# C3D_ReMix_Expansion_-_RJ45_Hat.net
KiCad netlist of a schematic drawn in EAGLE
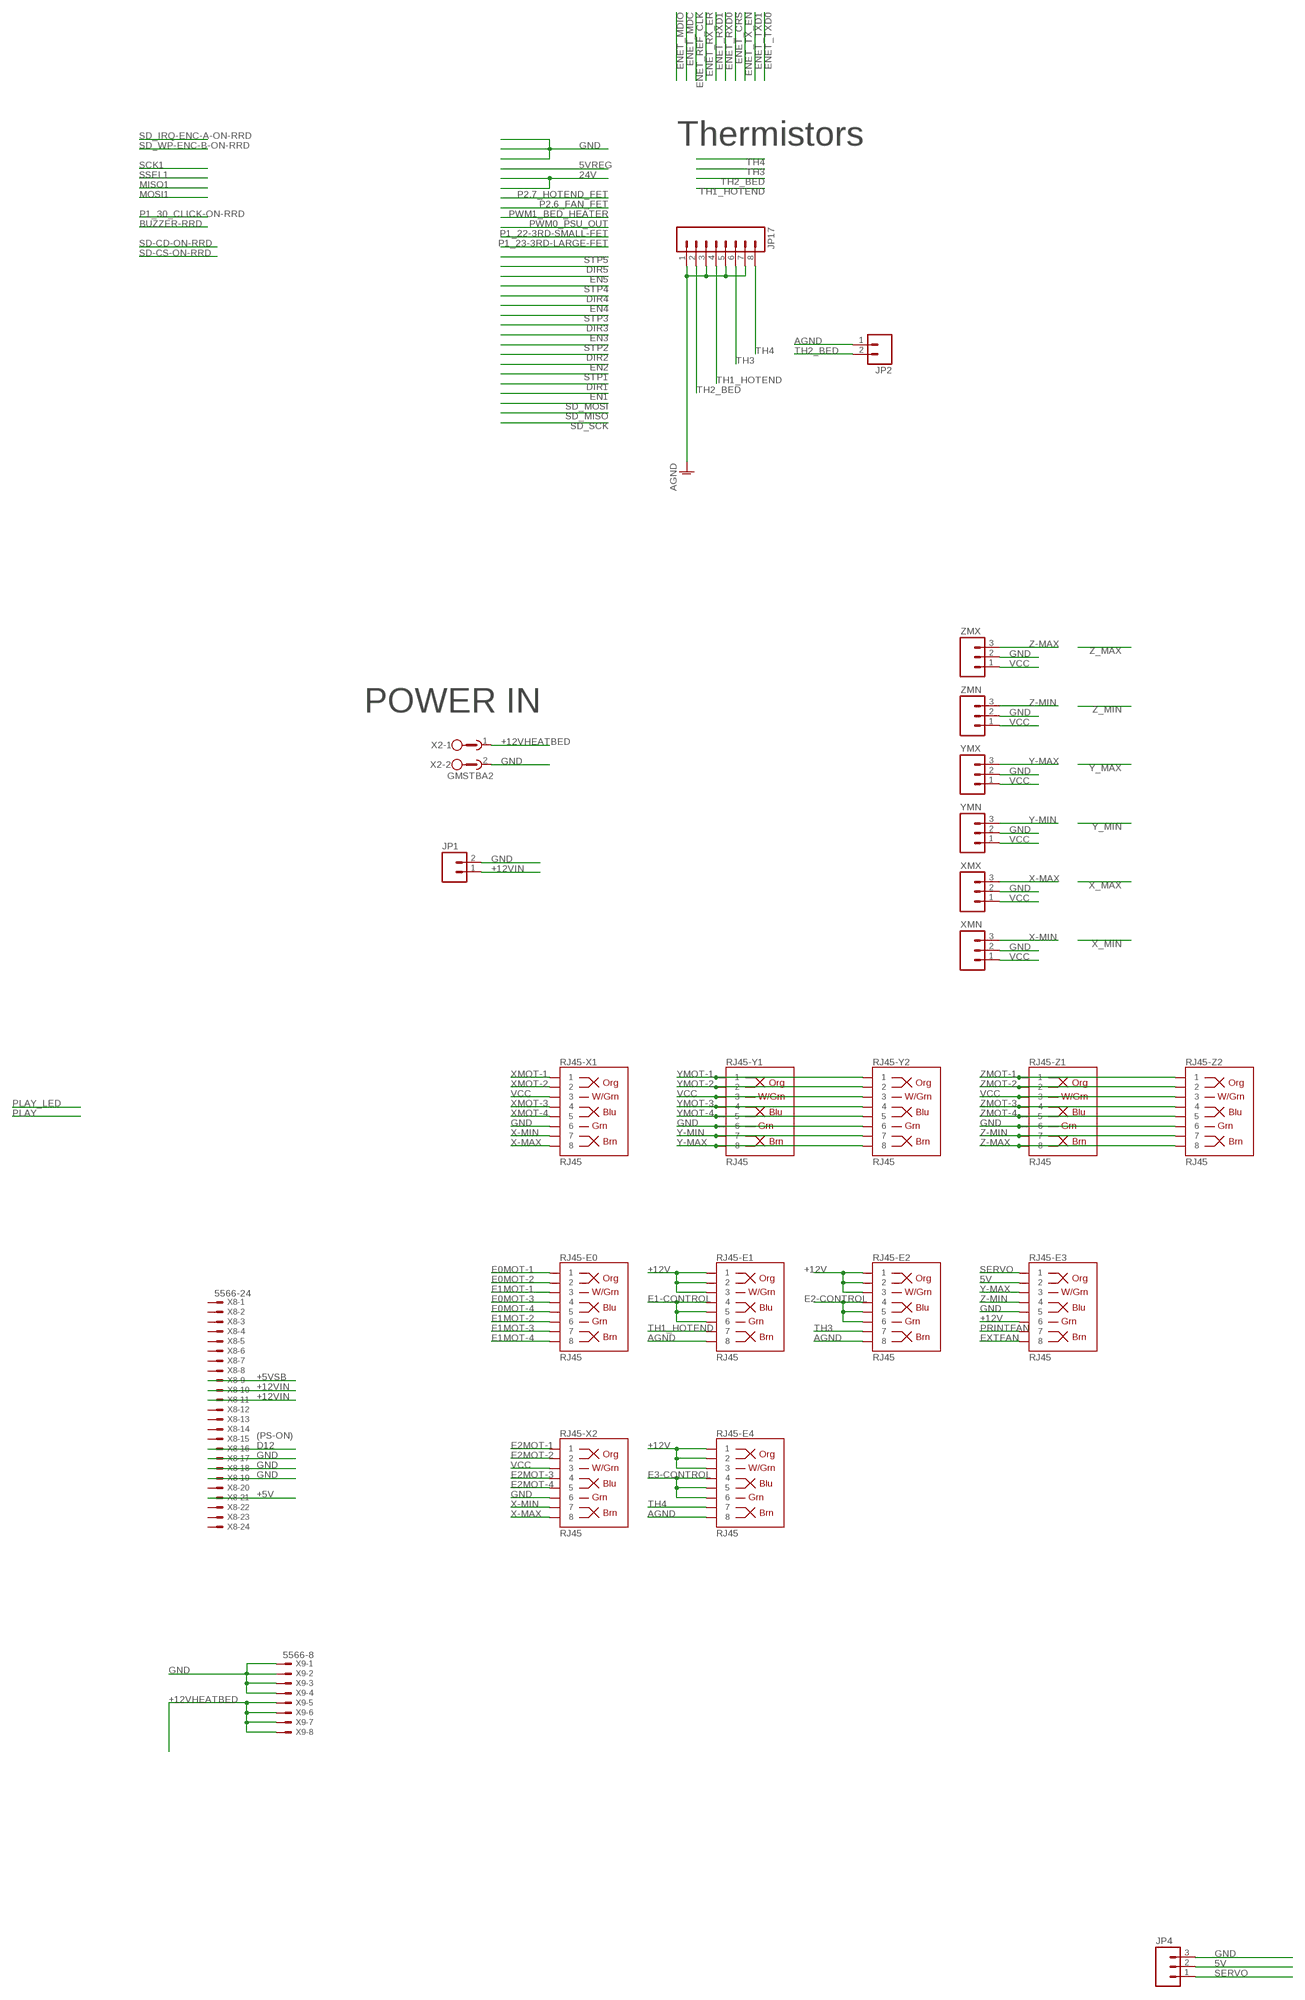
[diagram p0: schematic, sheet 1, part 1 of 2]
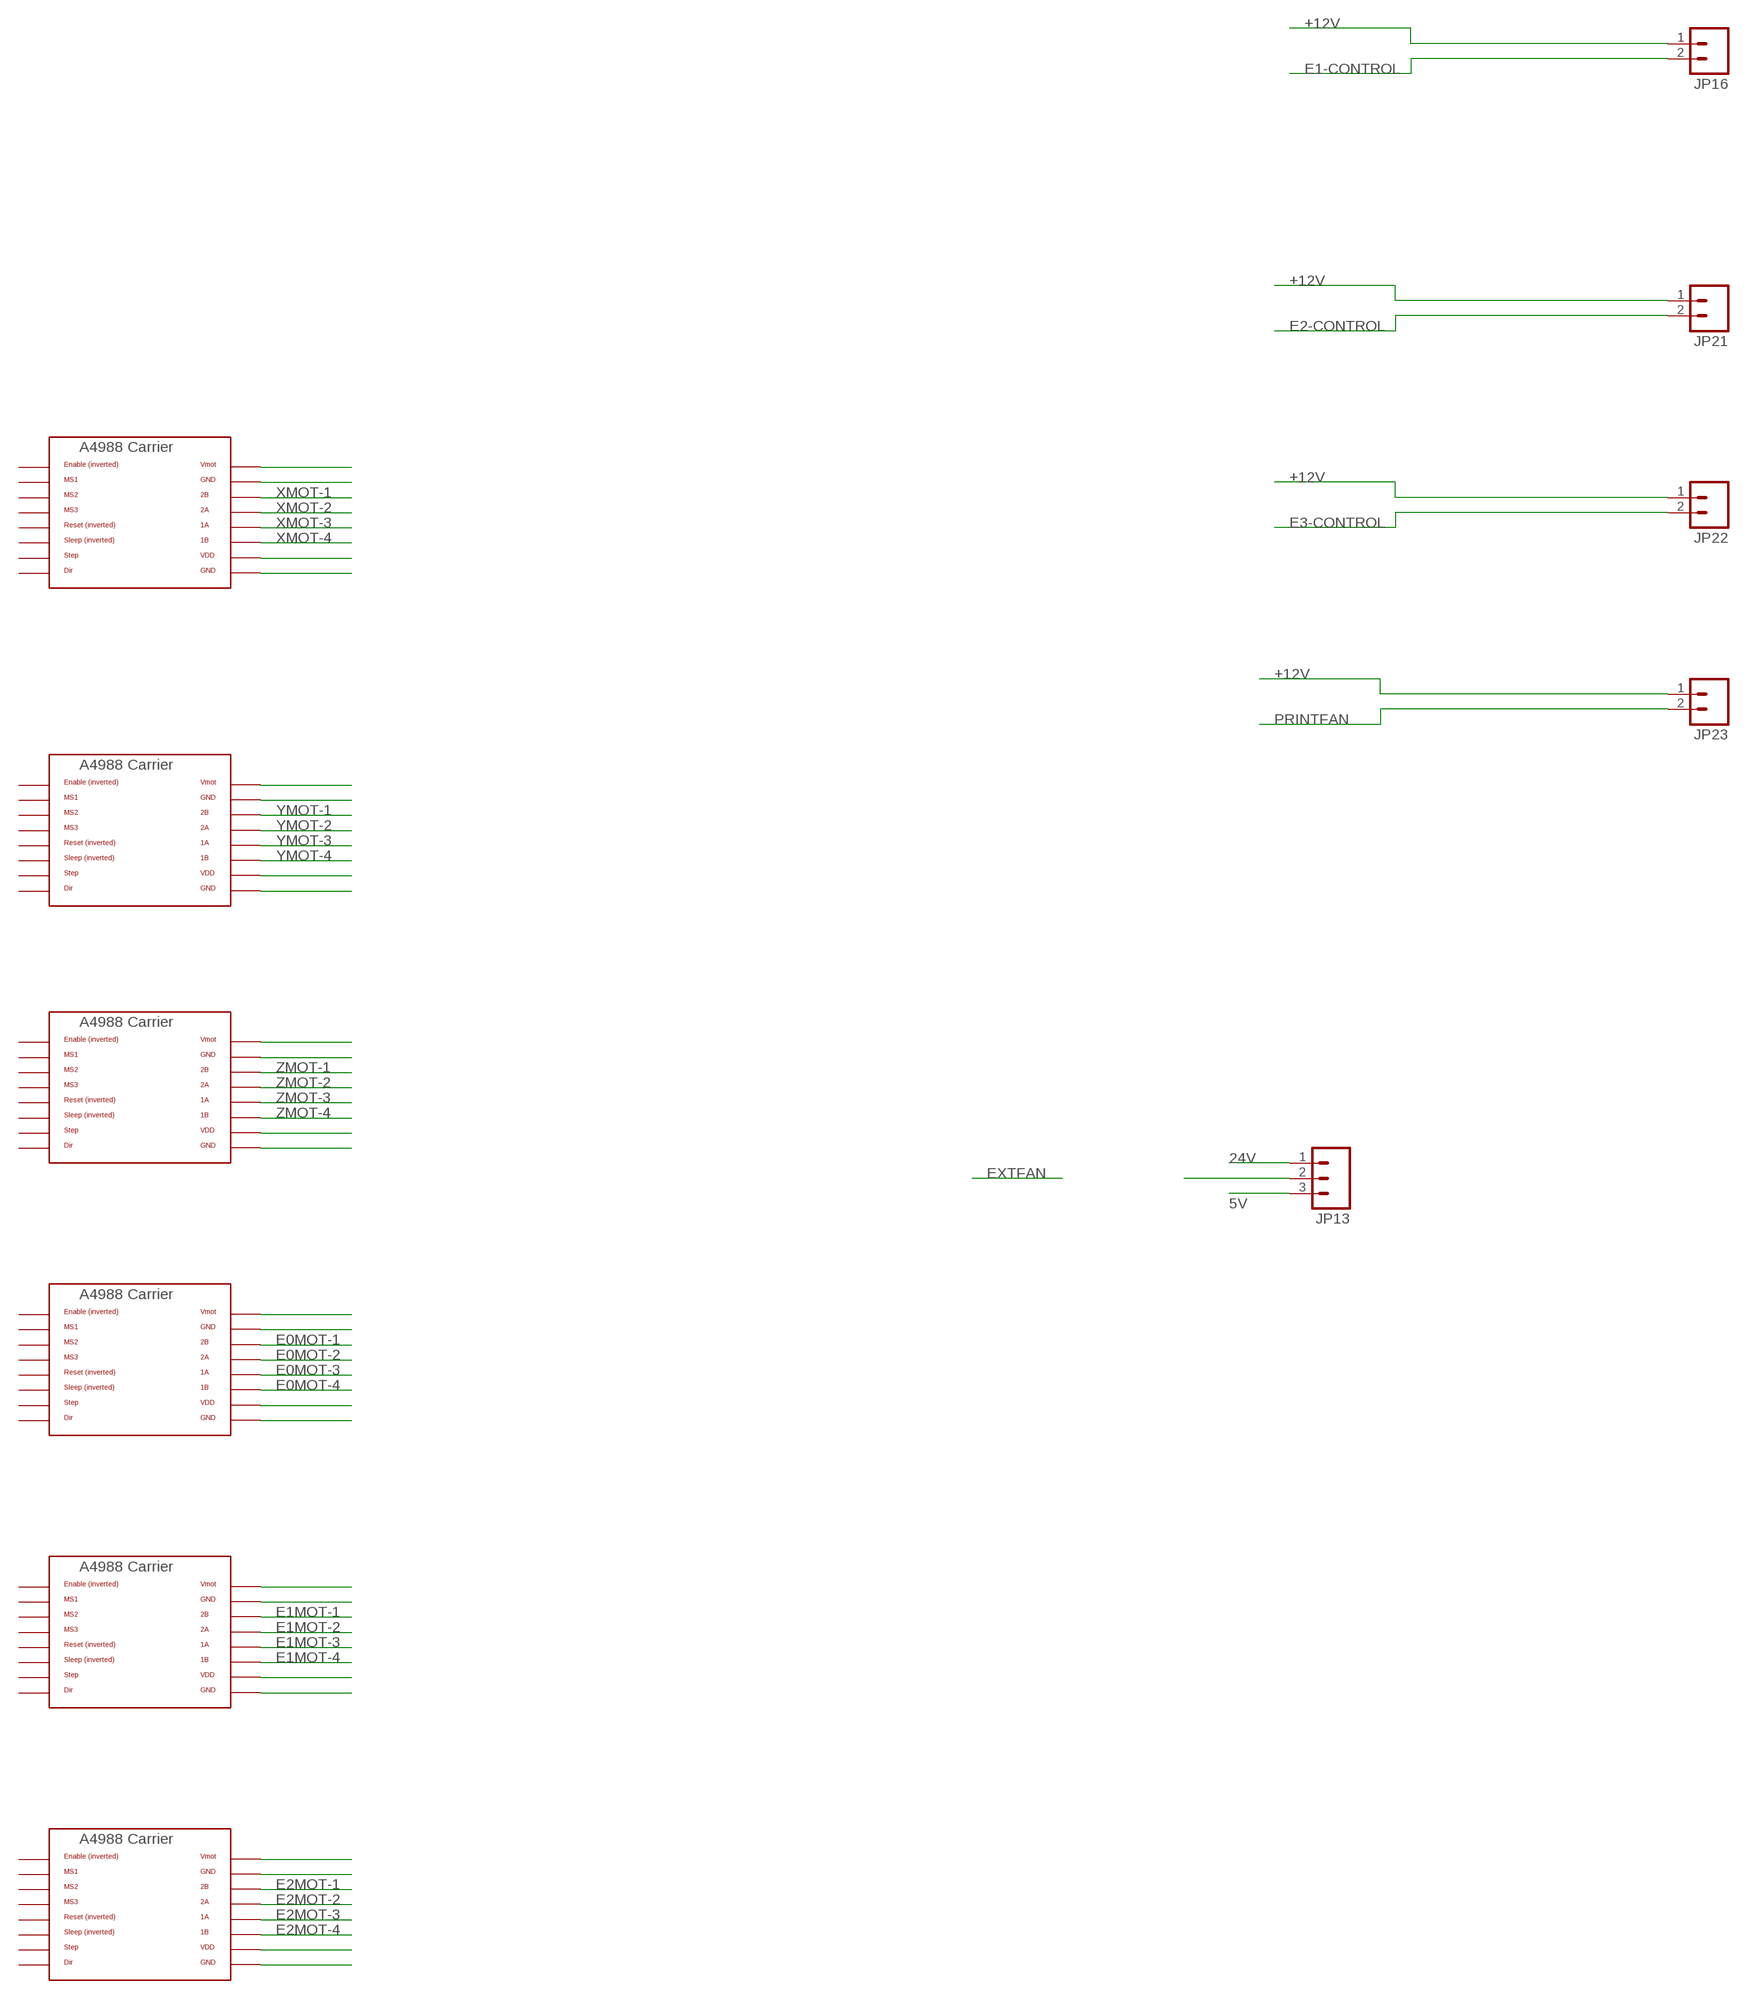
[diagram p1: schematic, sheet 1, part 2 of 2]

(export (version "E")
  (design (tool "Eeschema 10.0.6"))
  (components
    (comp (ref "JP1")
      (value "M025MM")
      (footprint "eagle-import:SCREWTERMINAL-5MM-2")
      (libsource (lib "eagle-import") (part "M025MM"))
    )
    (comp (ref "JP2")
      (value "M02LOCK")
      (footprint "eagle-import:1X02_LOCK")
      (libsource (lib "eagle-import") (part "M02LOCK"))
    )
    (comp (ref "JP4")
      (value "M03LOCK")
      (footprint "eagle-import:1X03_LOCK")
      (libsource (lib "eagle-import") (part "M03LOCK"))
    )
    (comp (ref "JP13")
      (value "M03LOCK_NO_SILK")
      (footprint "eagle-import:1X03_LOCK_NO_SILK")
      (libsource (lib "eagle-import") (part "M03LOCK_NO_SILK"))
    )
    (comp (ref "JP16")
      (value "M02LOCK")
      (footprint "eagle-import:1X02_LOCK")
      (libsource (lib "eagle-import") (part "M02LOCK"))
    )
    (comp (ref "JP17")
      (value "M08LOCK")
      (footprint "eagle-import:1X08_LOCK")
      (libsource (lib "eagle-import") (part "M08LOCK"))
    )
    (comp (ref "JP21")
      (value "M02LOCK")
      (footprint "eagle-import:1X02_LOCK")
      (libsource (lib "eagle-import") (part "M02LOCK"))
    )
    (comp (ref "JP22")
      (value "M02LOCK")
      (footprint "eagle-import:1X02_LOCK")
      (libsource (lib "eagle-import") (part "M02LOCK"))
    )
    (comp (ref "JP23")
      (value "M02LOCK")
      (footprint "eagle-import:1X02_LOCK")
      (libsource (lib "eagle-import") (part "M02LOCK"))
    )
    (comp (ref "RJ45-E0")
      (value "RJ45")
      (footprint "eagle-import:RJ45-8")
      (libsource (lib "eagle-import") (part "RJ45-8PTH"))
    )
    (comp (ref "RJ45-E1")
      (value "RJ45")
      (footprint "eagle-import:RJ45-8")
      (libsource (lib "eagle-import") (part "RJ45-8PTH"))
    )
    (comp (ref "RJ45-E2")
      (value "RJ45")
      (footprint "eagle-import:RJ45-8")
      (libsource (lib "eagle-import") (part "RJ45-8PTH"))
    )
    (comp (ref "RJ45-E3")
      (value "RJ45")
      (footprint "eagle-import:RJ45-8")
      (libsource (lib "eagle-import") (part "RJ45-8PTH"))
    )
    (comp (ref "RJ45-E4")
      (value "RJ45")
      (footprint "eagle-import:RJ45-8")
      (libsource (lib "eagle-import") (part "RJ45-8PTH"))
    )
    (comp (ref "RJ45-X1")
      (value "RJ45")
      (footprint "eagle-import:RJ45-8")
      (libsource (lib "eagle-import") (part "RJ45-8PTH"))
    )
    (comp (ref "RJ45-X2")
      (value "RJ45")
      (footprint "eagle-import:RJ45-8")
      (libsource (lib "eagle-import") (part "RJ45-8PTH"))
    )
    (comp (ref "RJ45-Y1")
      (value "RJ45")
      (footprint "eagle-import:RJ45-8")
      (libsource (lib "eagle-import") (part "RJ45-8PTH"))
    )
    (comp (ref "RJ45-Y2")
      (value "RJ45")
      (footprint "eagle-import:RJ45-8")
      (libsource (lib "eagle-import") (part "RJ45-8PTH"))
    )
    (comp (ref "RJ45-Z1")
      (value "RJ45")
      (footprint "eagle-import:RJ45-8")
      (libsource (lib "eagle-import") (part "RJ45-8PTH"))
    )
    (comp (ref "RJ45-Z2")
      (value "RJ45")
      (footprint "eagle-import:RJ45-8")
      (libsource (lib "eagle-import") (part "RJ45-8PTH"))
    )
    (comp (ref "U$1")
      (value "POLOLU_A4983CARRIER")
      (footprint "eagle-import:A4988BREAKOUT")
      (libsource (lib "eagle-import") (part "POLOLU_A4983CARRIER"))
    )
    (comp (ref "U$5")
      (value "POLOLU_A4983CARRIER")
      (footprint "eagle-import:A4988BREAKOUT")
      (libsource (lib "eagle-import") (part "POLOLU_A4983CARRIER"))
    )
    (comp (ref "U$6")
      (value "POLOLU_A4983CARRIER")
      (footprint "eagle-import:A4988BREAKOUT")
      (libsource (lib "eagle-import") (part "POLOLU_A4983CARRIER"))
    )
    (comp (ref "U$7")
      (value "POLOLU_A4983CARRIER")
      (footprint "eagle-import:A4988BREAKOUT")
      (libsource (lib "eagle-import") (part "POLOLU_A4983CARRIER"))
    )
    (comp (ref "U$8")
      (value "POLOLU_A4983CARRIER")
      (footprint "eagle-import:A4988BREAKOUT")
      (libsource (lib "eagle-import") (part "POLOLU_A4983CARRIER"))
    )
    (comp (ref "U$9")
      (value "POLOLU_A4983CARRIER")
      (footprint "eagle-import:A4988BREAKOUT")
      (libsource (lib "eagle-import") (part "POLOLU_A4983CARRIER"))
    )
    (comp (ref "X2")
      (value "GMSTBA2")
      (footprint "eagle-import:GMSTBA2")
      (fields (field (name "MF") "FARNELL") (field (name "MPN") "1757242"))
      (libsource (lib "eagle-import") (part "GMSTBA2"))
    )
    (comp (ref "X8")
      (value "5566-24")
      (footprint "eagle-import:5566-24")
      (libsource (lib "eagle-import") (part "5566-24"))
    )
    (comp (ref "X9")
      (value "5566-8")
      (footprint "eagle-import:5566-8")
      (libsource (lib "eagle-import") (part "5566-8"))
    )
    (comp (ref "XMN")
      (value "M03POLAR_LOCK")
      (footprint "eagle-import:MOLEX-1X3_LOCK")
      (libsource (lib "eagle-import") (part "M03POLAR_LOCK"))
    )
    (comp (ref "XMX")
      (value "M03POLAR_LOCK")
      (footprint "eagle-import:MOLEX-1X3_LOCK")
      (libsource (lib "eagle-import") (part "M03POLAR_LOCK"))
    )
    (comp (ref "YMN")
      (value "M03POLAR_LOCK")
      (footprint "eagle-import:MOLEX-1X3_LOCK")
      (libsource (lib "eagle-import") (part "M03POLAR_LOCK"))
    )
    (comp (ref "YMX")
      (value "M03POLAR_LOCK")
      (footprint "eagle-import:MOLEX-1X3_LOCK")
      (libsource (lib "eagle-import") (part "M03POLAR_LOCK"))
    )
    (comp (ref "ZMN")
      (value "M03POLAR_LOCK")
      (footprint "eagle-import:MOLEX-1X3_LOCK")
      (libsource (lib "eagle-import") (part "M03POLAR_LOCK"))
    )
    (comp (ref "ZMX")
      (value "M03POLAR_LOCK")
      (footprint "eagle-import:MOLEX-1X3_LOCK")
      (libsource (lib "eagle-import") (part "M03POLAR_LOCK"))
    )
  )
  (nets
    (net (code "1") (name "/+5V") (class "Default")
      (node (ref "X8") (pin "21") (pinfunction "S_21") (pintype "passive"))
    )
    (net (code "2") (name "/+5VSB") (class "Default")
      (node (ref "X8") (pin "9") (pinfunction "S_9") (pintype "passive"))
    )
    (net (code "3") (name "/+12V") (class "Default")
      (node (ref "JP16") (pin "1") (pinfunction "1_1") (pintype "passive"))
      (node (ref "JP21") (pin "1") (pinfunction "1_1") (pintype "passive"))
      (node (ref "JP22") (pin "1") (pinfunction "1_1") (pintype "passive"))
      (node (ref "JP23") (pin "1") (pinfunction "1_1") (pintype "passive"))
      (node (ref "RJ45-E1") (pin "1") (pinfunction "1_1") (pintype "bidirectional"))
      (node (ref "RJ45-E1") (pin "2") (pinfunction "2_2") (pintype "bidirectional"))
      (node (ref "RJ45-E1") (pin "3") (pinfunction "3_3") (pintype "bidirectional"))
      (node (ref "RJ45-E2") (pin "1") (pinfunction "1_1") (pintype "bidirectional"))
      (node (ref "RJ45-E2") (pin "2") (pinfunction "2_2") (pintype "bidirectional"))
      (node (ref "RJ45-E2") (pin "3") (pinfunction "3_3") (pintype "bidirectional"))
      (node (ref "RJ45-E3") (pin "6") (pinfunction "6_6") (pintype "bidirectional"))
      (node (ref "RJ45-E4") (pin "1") (pinfunction "1_1") (pintype "bidirectional"))
      (node (ref "RJ45-E4") (pin "2") (pinfunction "2_2") (pintype "bidirectional"))
      (node (ref "RJ45-E4") (pin "3") (pinfunction "3_3") (pintype "bidirectional"))
    )
    (net (code "4") (name "/+12VHEATBED") (class "Default")
      (node (ref "X2") (pin "1") (pinfunction "1_1") (pintype "passive"))
      (node (ref "X9") (pin "5") (pinfunction "S_5") (pintype "passive"))
      (node (ref "X9") (pin "6") (pinfunction "S_6") (pintype "passive"))
      (node (ref "X9") (pin "7") (pinfunction "S_7") (pintype "passive"))
      (node (ref "X9") (pin "8") (pinfunction "S_8") (pintype "passive"))
    )
    (net (code "5") (name "/+12VIN") (class "Default")
      (node (ref "JP1") (pin "1") (pinfunction "1_1") (pintype "passive"))
      (node (ref "X8") (pin "10") (pinfunction "S_10") (pintype "passive"))
      (node (ref "X8") (pin "11") (pinfunction "S_11") (pintype "passive"))
    )
    (net (code "6") (name "/5V") (class "Default")
      (node (ref "JP13") (pin "3") (pinfunction "3_3") (pintype "passive"))
      (node (ref "JP4") (pin "2") (pinfunction "2_2") (pintype "passive"))
      (node (ref "RJ45-E3") (pin "2") (pinfunction "2_2") (pintype "bidirectional"))
    )
    (net (code "8") (name "/24V") (class "Default")
      (node (ref "JP13") (pin "1") (pinfunction "1_1") (pintype "passive"))
    )
    (net (code "10") (name "/D12") (class "Default")
      (node (ref "X8") (pin "16") (pinfunction "S_16") (pintype "passive"))
    )
    (net (code "16") (name "/E0MOT-1") (class "Default")
      (node (ref "RJ45-E0") (pin "1") (pinfunction "1_1") (pintype "bidirectional"))
      (node (ref "U$7") (pin "2B") (pinfunction "2B_2B") (pintype "output"))
    )
    (net (code "17") (name "/E0MOT-2") (class "Default")
      (node (ref "RJ45-E0") (pin "2") (pinfunction "2_2") (pintype "bidirectional"))
      (node (ref "U$7") (pin "2A") (pinfunction "2A_2A") (pintype "output"))
    )
    (net (code "18") (name "/E0MOT-3") (class "Default")
      (node (ref "RJ45-E0") (pin "4") (pinfunction "4_4") (pintype "bidirectional"))
      (node (ref "U$7") (pin "1A") (pinfunction "1A_1A") (pintype "output"))
    )
    (net (code "19") (name "/E0MOT-4") (class "Default")
      (node (ref "RJ45-E0") (pin "5") (pinfunction "5_5") (pintype "bidirectional"))
      (node (ref "U$7") (pin "1B") (pinfunction "1B_1B") (pintype "output"))
    )
    (net (code "20") (name "/E1-CONTROL") (class "Default")
      (node (ref "JP16") (pin "2") (pinfunction "2_2") (pintype "passive"))
      (node (ref "RJ45-E1") (pin "4") (pinfunction "4_4") (pintype "bidirectional"))
      (node (ref "RJ45-E1") (pin "5") (pinfunction "5_5") (pintype "bidirectional"))
      (node (ref "RJ45-E1") (pin "6") (pinfunction "6_6") (pintype "bidirectional"))
    )
    (net (code "21") (name "/E1MOT-1") (class "Default")
      (node (ref "RJ45-E0") (pin "3") (pinfunction "3_3") (pintype "bidirectional"))
      (node (ref "U$8") (pin "2B") (pinfunction "2B_2B") (pintype "output"))
    )
    (net (code "22") (name "/E1MOT-2") (class "Default")
      (node (ref "RJ45-E0") (pin "6") (pinfunction "6_6") (pintype "bidirectional"))
      (node (ref "U$8") (pin "2A") (pinfunction "2A_2A") (pintype "output"))
    )
    (net (code "23") (name "/E1MOT-3") (class "Default")
      (node (ref "RJ45-E0") (pin "7") (pinfunction "7_7") (pintype "bidirectional"))
      (node (ref "U$8") (pin "1A") (pinfunction "1A_1A") (pintype "output"))
    )
    (net (code "24") (name "/E1MOT-4") (class "Default")
      (node (ref "RJ45-E0") (pin "8") (pinfunction "8_8") (pintype "bidirectional"))
      (node (ref "U$8") (pin "1B") (pinfunction "1B_1B") (pintype "output"))
    )
    (net (code "25") (name "/E2-CONTROL") (class "Default")
      (node (ref "JP21") (pin "2") (pinfunction "2_2") (pintype "passive"))
      (node (ref "RJ45-E2") (pin "4") (pinfunction "4_4") (pintype "bidirectional"))
      (node (ref "RJ45-E2") (pin "5") (pinfunction "5_5") (pintype "bidirectional"))
      (node (ref "RJ45-E2") (pin "6") (pinfunction "6_6") (pintype "bidirectional"))
    )
    (net (code "26") (name "/E2MOT-1") (class "Default")
      (node (ref "RJ45-X2") (pin "1") (pinfunction "1_1") (pintype "bidirectional"))
      (node (ref "U$9") (pin "2B") (pinfunction "2B_2B") (pintype "output"))
    )
    (net (code "27") (name "/E2MOT-2") (class "Default")
      (node (ref "RJ45-X2") (pin "2") (pinfunction "2_2") (pintype "bidirectional"))
      (node (ref "U$9") (pin "2A") (pinfunction "2A_2A") (pintype "output"))
    )
    (net (code "28") (name "/E2MOT-3") (class "Default")
      (node (ref "RJ45-X2") (pin "4") (pinfunction "4_4") (pintype "bidirectional"))
      (node (ref "U$9") (pin "1A") (pinfunction "1A_1A") (pintype "output"))
    )
    (net (code "29") (name "/E2MOT-4") (class "Default")
      (node (ref "RJ45-X2") (pin "5") (pinfunction "5_5") (pintype "bidirectional"))
      (node (ref "U$9") (pin "1B") (pinfunction "1B_1B") (pintype "output"))
    )
    (net (code "30") (name "/E3-CONTROL") (class "Default")
      (node (ref "JP22") (pin "2") (pinfunction "2_2") (pintype "passive"))
      (node (ref "RJ45-E4") (pin "4") (pinfunction "4_4") (pintype "bidirectional"))
      (node (ref "RJ45-E4") (pin "5") (pinfunction "5_5") (pintype "bidirectional"))
      (node (ref "RJ45-E4") (pin "6") (pinfunction "6_6") (pintype "bidirectional"))
    )
    (net (code "46") (name "/EXTFAN") (class "Default")
      (node (ref "RJ45-E3") (pin "8") (pinfunction "8_8") (pintype "bidirectional"))
    )
    (net (code "47") (name "/GND") (class "Default")
      (node (ref "JP1") (pin "2") (pinfunction "2_2") (pintype "passive"))
      (node (ref "JP4") (pin "3") (pinfunction "3_3") (pintype "passive"))
      (node (ref "RJ45-E3") (pin "5") (pinfunction "5_5") (pintype "bidirectional"))
      (node (ref "RJ45-X1") (pin "6") (pinfunction "6_6") (pintype "bidirectional"))
      (node (ref "RJ45-X2") (pin "6") (pinfunction "6_6") (pintype "bidirectional"))
      (node (ref "RJ45-Y1") (pin "6") (pinfunction "6_6") (pintype "bidirectional"))
      (node (ref "RJ45-Y2") (pin "6") (pinfunction "6_6") (pintype "bidirectional"))
      (node (ref "RJ45-Z1") (pin "6") (pinfunction "6_6") (pintype "bidirectional"))
      (node (ref "RJ45-Z2") (pin "6") (pinfunction "6_6") (pintype "bidirectional"))
      (node (ref "X2") (pin "2") (pinfunction "1_2") (pintype "passive"))
      (node (ref "X8") (pin "17") (pinfunction "S_17") (pintype "passive"))
      (node (ref "X8") (pin "18") (pinfunction "S_18") (pintype "passive"))
      (node (ref "X8") (pin "19") (pinfunction "S_19") (pintype "passive"))
      (node (ref "X9") (pin "1") (pinfunction "S_1") (pintype "passive"))
      (node (ref "X9") (pin "2") (pinfunction "S_2") (pintype "passive"))
      (node (ref "X9") (pin "3") (pinfunction "S_3") (pintype "passive"))
      (node (ref "X9") (pin "4") (pinfunction "S_4") (pintype "passive"))
      (node (ref "XMN") (pin "2") (pinfunction "2_2") (pintype "passive"))
      (node (ref "XMX") (pin "2") (pinfunction "2_2") (pintype "passive"))
      (node (ref "YMN") (pin "2") (pinfunction "2_2") (pintype "passive"))
      (node (ref "YMX") (pin "2") (pinfunction "2_2") (pintype "passive"))
      (node (ref "ZMN") (pin "2") (pinfunction "2_2") (pintype "passive"))
      (node (ref "ZMX") (pin "2") (pinfunction "2_2") (pintype "passive"))
    )
    (net (code "57") (name "/PRINTFAN") (class "Default")
      (node (ref "JP23") (pin "2") (pinfunction "2_2") (pintype "passive"))
      (node (ref "RJ45-E3") (pin "7") (pinfunction "7_7") (pintype "bidirectional"))
    )
    (net (code "68") (name "/SERVO") (class "Default")
      (node (ref "JP4") (pin "1") (pinfunction "1_1") (pintype "passive"))
      (node (ref "RJ45-E3") (pin "1") (pinfunction "1_1") (pintype "bidirectional"))
    )
    (net (code "75") (name "/TH1_HOTEND") (class "Default")
      (node (ref "JP17") (pin "4") (pinfunction "4_4") (pintype "passive"))
      (node (ref "RJ45-E1") (pin "7") (pinfunction "7_7") (pintype "bidirectional"))
    )
    (net (code "76") (name "/TH2_BED") (class "Default")
      (node (ref "JP17") (pin "2") (pinfunction "2_2") (pintype "passive"))
      (node (ref "JP2") (pin "2") (pinfunction "2_2") (pintype "passive"))
    )
    (net (code "77") (name "/TH3") (class "Default")
      (node (ref "JP17") (pin "6") (pinfunction "6_6") (pintype "passive"))
      (node (ref "RJ45-E2") (pin "7") (pinfunction "7_7") (pintype "bidirectional"))
    )
    (net (code "78") (name "/TH4") (class "Default")
      (node (ref "JP17") (pin "8") (pinfunction "8_8") (pintype "passive"))
      (node (ref "RJ45-E4") (pin "7") (pinfunction "7_7") (pintype "bidirectional"))
    )
    (net (code "79") (name "/VCC") (class "Default")
      (node (ref "RJ45-X1") (pin "3") (pinfunction "3_3") (pintype "bidirectional"))
      (node (ref "RJ45-X2") (pin "3") (pinfunction "3_3") (pintype "bidirectional"))
      (node (ref "RJ45-Y1") (pin "3") (pinfunction "3_3") (pintype "bidirectional"))
      (node (ref "RJ45-Y2") (pin "3") (pinfunction "3_3") (pintype "bidirectional"))
      (node (ref "RJ45-Z1") (pin "3") (pinfunction "3_3") (pintype "bidirectional"))
      (node (ref "RJ45-Z2") (pin "3") (pinfunction "3_3") (pintype "bidirectional"))
      (node (ref "XMN") (pin "1") (pinfunction "1_1") (pintype "passive"))
      (node (ref "XMX") (pin "1") (pinfunction "1_1") (pintype "passive"))
      (node (ref "YMN") (pin "1") (pinfunction "1_1") (pintype "passive"))
      (node (ref "YMX") (pin "1") (pinfunction "1_1") (pintype "passive"))
      (node (ref "ZMN") (pin "1") (pinfunction "1_1") (pintype "passive"))
      (node (ref "ZMX") (pin "1") (pinfunction "1_1") (pintype "passive"))
    )
    (net (code "80") (name "/X-MAX") (class "Default")
      (node (ref "RJ45-X1") (pin "8") (pinfunction "8_8") (pintype "bidirectional"))
      (node (ref "RJ45-X2") (pin "8") (pinfunction "8_8") (pintype "bidirectional"))
      (node (ref "XMX") (pin "3") (pinfunction "3_3") (pintype "passive"))
    )
    (net (code "81") (name "/X-MIN") (class "Default")
      (node (ref "RJ45-X1") (pin "7") (pinfunction "7_7") (pintype "bidirectional"))
      (node (ref "RJ45-X2") (pin "7") (pinfunction "7_7") (pintype "bidirectional"))
      (node (ref "XMN") (pin "3") (pinfunction "3_3") (pintype "passive"))
    )
    (net (code "82") (name "/XMOT-1") (class "Default")
      (node (ref "RJ45-X1") (pin "1") (pinfunction "1_1") (pintype "bidirectional"))
      (node (ref "U$1") (pin "2B") (pinfunction "2B_2B") (pintype "output"))
    )
    (net (code "83") (name "/XMOT-2") (class "Default")
      (node (ref "RJ45-X1") (pin "2") (pinfunction "2_2") (pintype "bidirectional"))
      (node (ref "U$1") (pin "2A") (pinfunction "2A_2A") (pintype "output"))
    )
    (net (code "84") (name "/XMOT-3") (class "Default")
      (node (ref "RJ45-X1") (pin "4") (pinfunction "4_4") (pintype "bidirectional"))
      (node (ref "U$1") (pin "1A") (pinfunction "1A_1A") (pintype "output"))
    )
    (net (code "85") (name "/XMOT-4") (class "Default")
      (node (ref "RJ45-X1") (pin "5") (pinfunction "5_5") (pintype "bidirectional"))
      (node (ref "U$1") (pin "1B") (pinfunction "1B_1B") (pintype "output"))
    )
    (net (code "88") (name "/Y-MAX") (class "Default")
      (node (ref "RJ45-E3") (pin "3") (pinfunction "3_3") (pintype "bidirectional"))
      (node (ref "RJ45-Y1") (pin "8") (pinfunction "8_8") (pintype "bidirectional"))
      (node (ref "RJ45-Y2") (pin "8") (pinfunction "8_8") (pintype "bidirectional"))
      (node (ref "YMX") (pin "3") (pinfunction "3_3") (pintype "passive"))
    )
    (net (code "89") (name "/Y-MIN") (class "Default")
      (node (ref "RJ45-Y1") (pin "7") (pinfunction "7_7") (pintype "bidirectional"))
      (node (ref "RJ45-Y2") (pin "7") (pinfunction "7_7") (pintype "bidirectional"))
      (node (ref "YMN") (pin "3") (pinfunction "3_3") (pintype "passive"))
    )
    (net (code "90") (name "/YMOT-1") (class "Default")
      (node (ref "RJ45-Y1") (pin "1") (pinfunction "1_1") (pintype "bidirectional"))
      (node (ref "RJ45-Y2") (pin "1") (pinfunction "1_1") (pintype "bidirectional"))
      (node (ref "U$5") (pin "2B") (pinfunction "2B_2B") (pintype "output"))
    )
    (net (code "91") (name "/YMOT-2") (class "Default")
      (node (ref "RJ45-Y1") (pin "2") (pinfunction "2_2") (pintype "bidirectional"))
      (node (ref "RJ45-Y2") (pin "2") (pinfunction "2_2") (pintype "bidirectional"))
      (node (ref "U$5") (pin "2A") (pinfunction "2A_2A") (pintype "output"))
    )
    (net (code "92") (name "/YMOT-3") (class "Default")
      (node (ref "RJ45-Y1") (pin "4") (pinfunction "4_4") (pintype "bidirectional"))
      (node (ref "RJ45-Y2") (pin "4") (pinfunction "4_4") (pintype "bidirectional"))
      (node (ref "U$5") (pin "1A") (pinfunction "1A_1A") (pintype "output"))
    )
    (net (code "93") (name "/YMOT-4") (class "Default")
      (node (ref "RJ45-Y1") (pin "5") (pinfunction "5_5") (pintype "bidirectional"))
      (node (ref "RJ45-Y2") (pin "5") (pinfunction "5_5") (pintype "bidirectional"))
      (node (ref "U$5") (pin "1B") (pinfunction "1B_1B") (pintype "output"))
    )
    (net (code "96") (name "/Z-MAX") (class "Default")
      (node (ref "RJ45-Z1") (pin "8") (pinfunction "8_8") (pintype "bidirectional"))
      (node (ref "RJ45-Z2") (pin "8") (pinfunction "8_8") (pintype "bidirectional"))
      (node (ref "ZMX") (pin "3") (pinfunction "3_3") (pintype "passive"))
    )
    (net (code "97") (name "/Z-MIN") (class "Default")
      (node (ref "RJ45-E3") (pin "4") (pinfunction "4_4") (pintype "bidirectional"))
      (node (ref "RJ45-Z1") (pin "7") (pinfunction "7_7") (pintype "bidirectional"))
      (node (ref "RJ45-Z2") (pin "7") (pinfunction "7_7") (pintype "bidirectional"))
      (node (ref "ZMN") (pin "3") (pinfunction "3_3") (pintype "passive"))
    )
    (net (code "98") (name "/ZMOT-1") (class "Default")
      (node (ref "RJ45-Z1") (pin "1") (pinfunction "1_1") (pintype "bidirectional"))
      (node (ref "RJ45-Z2") (pin "1") (pinfunction "1_1") (pintype "bidirectional"))
      (node (ref "U$6") (pin "2B") (pinfunction "2B_2B") (pintype "output"))
    )
    (net (code "99") (name "/ZMOT-2") (class "Default")
      (node (ref "RJ45-Z1") (pin "2") (pinfunction "2_2") (pintype "bidirectional"))
      (node (ref "RJ45-Z2") (pin "2") (pinfunction "2_2") (pintype "bidirectional"))
      (node (ref "U$6") (pin "2A") (pinfunction "2A_2A") (pintype "output"))
    )
    (net (code "100") (name "/ZMOT-3") (class "Default")
      (node (ref "RJ45-Z1") (pin "4") (pinfunction "4_4") (pintype "bidirectional"))
      (node (ref "RJ45-Z2") (pin "4") (pinfunction "4_4") (pintype "bidirectional"))
      (node (ref "U$6") (pin "1A") (pinfunction "1A_1A") (pintype "output"))
    )
    (net (code "101") (name "/ZMOT-4") (class "Default")
      (node (ref "RJ45-Z1") (pin "5") (pinfunction "5_5") (pintype "bidirectional"))
      (node (ref "RJ45-Z2") (pin "5") (pinfunction "5_5") (pintype "bidirectional"))
      (node (ref "U$6") (pin "1B") (pinfunction "1B_1B") (pintype "output"))
    )
    (net (code "104") (name "AGND") (class "Default")
      (node (ref "JP17") (pin "1") (pinfunction "1_1") (pintype "passive"))
      (node (ref "JP17") (pin "3") (pinfunction "3_3") (pintype "passive"))
      (node (ref "JP17") (pin "5") (pinfunction "5_5") (pintype "passive"))
      (node (ref "JP17") (pin "7") (pinfunction "7_7") (pintype "passive"))
      (node (ref "JP2") (pin "1") (pinfunction "1_1") (pintype "passive"))
      (node (ref "RJ45-E1") (pin "8") (pinfunction "8_8") (pintype "bidirectional"))
      (node (ref "RJ45-E2") (pin "8") (pinfunction "8_8") (pintype "bidirectional"))
      (node (ref "RJ45-E4") (pin "8") (pinfunction "8_8") (pintype "bidirectional"))
    )
    (net (code "105") (name "unconnected-(JP13-Pad2)") (class "Default")
      (node (ref "JP13") (pin "2") (pinfunction "2_2") (pintype "passive"))
    )
    (net (code "106") (name "unconnected-(U$1-GND-PadGND@0)") (class "Default")
      (node (ref "U$1") (pin "GND@0") (pinfunction "GND_GND@0") (pintype "power_in"))
    )
    (net (code "107") (name "unconnected-(U$1-PadDIR)") (class "Default")
      (node (ref "U$1") (pin "DIR") (pinfunction "DIR_DIR") (pintype "input"))
    )
    (net (code "108") (name "unconnected-(U$1-PadEN)") (class "Default")
      (node (ref "U$1") (pin "EN") (pinfunction "EN_EN") (pintype "input"))
    )
    (net (code "109") (name "unconnected-(U$1-PadGND)") (class "Default")
      (node (ref "U$1") (pin "GND") (pinfunction "GND_GND") (pintype "power_in"))
    )
    (net (code "110") (name "unconnected-(U$1-PadMS1)") (class "Default")
      (node (ref "U$1") (pin "MS1") (pinfunction "MS1_MS1") (pintype "input"))
    )
    (net (code "111") (name "unconnected-(U$1-PadMS2)") (class "Default")
      (node (ref "U$1") (pin "MS2") (pinfunction "MS2_MS2") (pintype "input"))
    )
    (net (code "112") (name "unconnected-(U$1-PadMS3)") (class "Default")
      (node (ref "U$1") (pin "MS3") (pinfunction "MS3_MS3") (pintype "input"))
    )
    (net (code "113") (name "unconnected-(U$1-PadRST)") (class "Default")
      (node (ref "U$1") (pin "RST") (pinfunction "RST_RST") (pintype "input"))
    )
    (net (code "114") (name "unconnected-(U$1-PadSTEP)") (class "Default")
      (node (ref "U$1") (pin "STEP") (pinfunction "STEP_STEP") (pintype "input"))
    )
    (net (code "115") (name "unconnected-(U$1-PadVDD)") (class "Default")
      (node (ref "U$1") (pin "VDD") (pinfunction "VDD_VDD") (pintype "power_in"))
    )
    (net (code "116") (name "unconnected-(U$1-PadVMOT)") (class "Default")
      (node (ref "U$1") (pin "VMOT") (pinfunction "VMOT_VMOT") (pintype "power_in"))
    )
    (net (code "117") (name "unconnected-(U$1-SLEEP-PadSLP)") (class "Default")
      (node (ref "U$1") (pin "SLP") (pinfunction "SLEEP_SLP") (pintype "input"))
    )
    (net (code "118") (name "unconnected-(U$5-GND-PadGND@0)") (class "Default")
      (node (ref "U$5") (pin "GND@0") (pinfunction "GND_GND@0") (pintype "power_in"))
    )
    (net (code "119") (name "unconnected-(U$5-PadDIR)") (class "Default")
      (node (ref "U$5") (pin "DIR") (pinfunction "DIR_DIR") (pintype "input"))
    )
    (net (code "120") (name "unconnected-(U$5-PadEN)") (class "Default")
      (node (ref "U$5") (pin "EN") (pinfunction "EN_EN") (pintype "input"))
    )
    (net (code "121") (name "unconnected-(U$5-PadGND)") (class "Default")
      (node (ref "U$5") (pin "GND") (pinfunction "GND_GND") (pintype "power_in"))
    )
    (net (code "122") (name "unconnected-(U$5-PadMS1)") (class "Default")
      (node (ref "U$5") (pin "MS1") (pinfunction "MS1_MS1") (pintype "input"))
    )
    (net (code "123") (name "unconnected-(U$5-PadMS2)") (class "Default")
      (node (ref "U$5") (pin "MS2") (pinfunction "MS2_MS2") (pintype "input"))
    )
    (net (code "124") (name "unconnected-(U$5-PadMS3)") (class "Default")
      (node (ref "U$5") (pin "MS3") (pinfunction "MS3_MS3") (pintype "input"))
    )
    (net (code "125") (name "unconnected-(U$5-PadRST)") (class "Default")
      (node (ref "U$5") (pin "RST") (pinfunction "RST_RST") (pintype "input"))
    )
    (net (code "126") (name "unconnected-(U$5-PadSTEP)") (class "Default")
      (node (ref "U$5") (pin "STEP") (pinfunction "STEP_STEP") (pintype "input"))
    )
    (net (code "127") (name "unconnected-(U$5-PadVDD)") (class "Default")
      (node (ref "U$5") (pin "VDD") (pinfunction "VDD_VDD") (pintype "power_in"))
    )
    (net (code "128") (name "unconnected-(U$5-PadVMOT)") (class "Default")
      (node (ref "U$5") (pin "VMOT") (pinfunction "VMOT_VMOT") (pintype "power_in"))
    )
    (net (code "129") (name "unconnected-(U$5-SLEEP-PadSLP)") (class "Default")
      (node (ref "U$5") (pin "SLP") (pinfunction "SLEEP_SLP") (pintype "input"))
    )
    (net (code "130") (name "unconnected-(U$6-GND-PadGND@0)") (class "Default")
      (node (ref "U$6") (pin "GND@0") (pinfunction "GND_GND@0") (pintype "power_in"))
    )
    (net (code "131") (name "unconnected-(U$6-PadDIR)") (class "Default")
      (node (ref "U$6") (pin "DIR") (pinfunction "DIR_DIR") (pintype "input"))
    )
    (net (code "132") (name "unconnected-(U$6-PadEN)") (class "Default")
      (node (ref "U$6") (pin "EN") (pinfunction "EN_EN") (pintype "input"))
    )
    (net (code "133") (name "unconnected-(U$6-PadGND)") (class "Default")
      (node (ref "U$6") (pin "GND") (pinfunction "GND_GND") (pintype "power_in"))
    )
    (net (code "134") (name "unconnected-(U$6-PadMS1)") (class "Default")
      (node (ref "U$6") (pin "MS1") (pinfunction "MS1_MS1") (pintype "input"))
    )
    (net (code "135") (name "unconnected-(U$6-PadMS2)") (class "Default")
      (node (ref "U$6") (pin "MS2") (pinfunction "MS2_MS2") (pintype "input"))
    )
    (net (code "136") (name "unconnected-(U$6-PadMS3)") (class "Default")
      (node (ref "U$6") (pin "MS3") (pinfunction "MS3_MS3") (pintype "input"))
    )
    (net (code "137") (name "unconnected-(U$6-PadRST)") (class "Default")
      (node (ref "U$6") (pin "RST") (pinfunction "RST_RST") (pintype "input"))
    )
    (net (code "138") (name "unconnected-(U$6-PadSTEP)") (class "Default")
      (node (ref "U$6") (pin "STEP") (pinfunction "STEP_STEP") (pintype "input"))
    )
    (net (code "139") (name "unconnected-(U$6-PadVDD)") (class "Default")
      (node (ref "U$6") (pin "VDD") (pinfunction "VDD_VDD") (pintype "power_in"))
    )
    (net (code "140") (name "unconnected-(U$6-PadVMOT)") (class "Default")
      (node (ref "U$6") (pin "VMOT") (pinfunction "VMOT_VMOT") (pintype "power_in"))
    )
    (net (code "141") (name "unconnected-(U$6-SLEEP-PadSLP)") (class "Default")
      (node (ref "U$6") (pin "SLP") (pinfunction "SLEEP_SLP") (pintype "input"))
    )
    (net (code "142") (name "unconnected-(U$7-GND-PadGND@0)") (class "Default")
      (node (ref "U$7") (pin "GND@0") (pinfunction "GND_GND@0") (pintype "power_in"))
    )
    (net (code "143") (name "unconnected-(U$7-PadDIR)") (class "Default")
      (node (ref "U$7") (pin "DIR") (pinfunction "DIR_DIR") (pintype "input"))
    )
    (net (code "144") (name "unconnected-(U$7-PadEN)") (class "Default")
      (node (ref "U$7") (pin "EN") (pinfunction "EN_EN") (pintype "input"))
    )
    (net (code "145") (name "unconnected-(U$7-PadGND)") (class "Default")
      (node (ref "U$7") (pin "GND") (pinfunction "GND_GND") (pintype "power_in"))
    )
    (net (code "146") (name "unconnected-(U$7-PadMS1)") (class "Default")
      (node (ref "U$7") (pin "MS1") (pinfunction "MS1_MS1") (pintype "input"))
    )
    (net (code "147") (name "unconnected-(U$7-PadMS2)") (class "Default")
      (node (ref "U$7") (pin "MS2") (pinfunction "MS2_MS2") (pintype "input"))
    )
    (net (code "148") (name "unconnected-(U$7-PadMS3)") (class "Default")
      (node (ref "U$7") (pin "MS3") (pinfunction "MS3_MS3") (pintype "input"))
    )
    (net (code "149") (name "unconnected-(U$7-PadRST)") (class "Default")
      (node (ref "U$7") (pin "RST") (pinfunction "RST_RST") (pintype "input"))
    )
    (net (code "150") (name "unconnected-(U$7-PadSTEP)") (class "Default")
      (node (ref "U$7") (pin "STEP") (pinfunction "STEP_STEP") (pintype "input"))
    )
    (net (code "151") (name "unconnected-(U$7-PadVDD)") (class "Default")
      (node (ref "U$7") (pin "VDD") (pinfunction "VDD_VDD") (pintype "power_in"))
    )
    (net (code "152") (name "unconnected-(U$7-PadVMOT)") (class "Default")
      (node (ref "U$7") (pin "VMOT") (pinfunction "VMOT_VMOT") (pintype "power_in"))
    )
    (net (code "153") (name "unconnected-(U$7-SLEEP-PadSLP)") (class "Default")
      (node (ref "U$7") (pin "SLP") (pinfunction "SLEEP_SLP") (pintype "input"))
    )
    (net (code "154") (name "unconnected-(U$8-GND-PadGND@0)") (class "Default")
      (node (ref "U$8") (pin "GND@0") (pinfunction "GND_GND@0") (pintype "power_in"))
    )
    (net (code "155") (name "unconnected-(U$8-PadDIR)") (class "Default")
      (node (ref "U$8") (pin "DIR") (pinfunction "DIR_DIR") (pintype "input"))
    )
    (net (code "156") (name "unconnected-(U$8-PadEN)") (class "Default")
      (node (ref "U$8") (pin "EN") (pinfunction "EN_EN") (pintype "input"))
    )
    (net (code "157") (name "unconnected-(U$8-PadGND)") (class "Default")
      (node (ref "U$8") (pin "GND") (pinfunction "GND_GND") (pintype "power_in"))
    )
    (net (code "158") (name "unconnected-(U$8-PadMS1)") (class "Default")
      (node (ref "U$8") (pin "MS1") (pinfunction "MS1_MS1") (pintype "input"))
    )
    (net (code "159") (name "unconnected-(U$8-PadMS2)") (class "Default")
      (node (ref "U$8") (pin "MS2") (pinfunction "MS2_MS2") (pintype "input"))
    )
    (net (code "160") (name "unconnected-(U$8-PadMS3)") (class "Default")
      (node (ref "U$8") (pin "MS3") (pinfunction "MS3_MS3") (pintype "input"))
    )
    (net (code "161") (name "unconnected-(U$8-PadRST)") (class "Default")
      (node (ref "U$8") (pin "RST") (pinfunction "RST_RST") (pintype "input"))
    )
    (net (code "162") (name "unconnected-(U$8-PadSTEP)") (class "Default")
      (node (ref "U$8") (pin "STEP") (pinfunction "STEP_STEP") (pintype "input"))
    )
    (net (code "163") (name "unconnected-(U$8-PadVDD)") (class "Default")
      (node (ref "U$8") (pin "VDD") (pinfunction "VDD_VDD") (pintype "power_in"))
    )
    (net (code "164") (name "unconnected-(U$8-PadVMOT)") (class "Default")
      (node (ref "U$8") (pin "VMOT") (pinfunction "VMOT_VMOT") (pintype "power_in"))
    )
    (net (code "165") (name "unconnected-(U$8-SLEEP-PadSLP)") (class "Default")
      (node (ref "U$8") (pin "SLP") (pinfunction "SLEEP_SLP") (pintype "input"))
    )
    (net (code "166") (name "unconnected-(U$9-GND-PadGND@0)") (class "Default")
      (node (ref "U$9") (pin "GND@0") (pinfunction "GND_GND@0") (pintype "power_in"))
    )
    (net (code "167") (name "unconnected-(U$9-PadDIR)") (class "Default")
      (node (ref "U$9") (pin "DIR") (pinfunction "DIR_DIR") (pintype "input"))
    )
    (net (code "168") (name "unconnected-(U$9-PadEN)") (class "Default")
      (node (ref "U$9") (pin "EN") (pinfunction "EN_EN") (pintype "input"))
    )
    (net (code "169") (name "unconnected-(U$9-PadGND)") (class "Default")
      (node (ref "U$9") (pin "GND") (pinfunction "GND_GND") (pintype "power_in"))
    )
    (net (code "170") (name "unconnected-(U$9-PadMS1)") (class "Default")
      (node (ref "U$9") (pin "MS1") (pinfunction "MS1_MS1") (pintype "input"))
    )
    (net (code "171") (name "unconnected-(U$9-PadMS2)") (class "Default")
      (node (ref "U$9") (pin "MS2") (pinfunction "MS2_MS2") (pintype "input"))
    )
    (net (code "172") (name "unconnected-(U$9-PadMS3)") (class "Default")
      (node (ref "U$9") (pin "MS3") (pinfunction "MS3_MS3") (pintype "input"))
    )
    (net (code "173") (name "unconnected-(U$9-PadRST)") (class "Default")
      (node (ref "U$9") (pin "RST") (pinfunction "RST_RST") (pintype "input"))
    )
    (net (code "174") (name "unconnected-(U$9-PadSTEP)") (class "Default")
      (node (ref "U$9") (pin "STEP") (pinfunction "STEP_STEP") (pintype "input"))
    )
    (net (code "175") (name "unconnected-(U$9-PadVDD)") (class "Default")
      (node (ref "U$9") (pin "VDD") (pinfunction "VDD_VDD") (pintype "power_in"))
    )
    (net (code "176") (name "unconnected-(U$9-PadVMOT)") (class "Default")
      (node (ref "U$9") (pin "VMOT") (pinfunction "VMOT_VMOT") (pintype "power_in"))
    )
    (net (code "177") (name "unconnected-(U$9-SLEEP-PadSLP)") (class "Default")
      (node (ref "U$9") (pin "SLP") (pinfunction "SLEEP_SLP") (pintype "input"))
    )
    (net (code "178") (name "unconnected-(X8A-S-Pad1)") (class "Default")
      (node (ref "X8") (pin "1") (pinfunction "S_1") (pintype "passive"))
    )
    (net (code "179") (name "unconnected-(X8D-S-Pad12)") (class "Default")
      (node (ref "X8") (pin "12") (pinfunction "S_12") (pintype "passive"))
    )
    (net (code "180") (name "unconnected-(X8E-S-Pad13)") (class "Default")
      (node (ref "X8") (pin "13") (pinfunction "S_13") (pintype "passive"))
    )
    (net (code "181") (name "unconnected-(X8F-S-Pad14)") (class "Default")
      (node (ref "X8") (pin "14") (pinfunction "S_14") (pintype "passive"))
    )
    (net (code "182") (name "unconnected-(X8G-S-Pad15)") (class "Default")
      (node (ref "X8") (pin "15") (pinfunction "S_15") (pintype "passive"))
    )
    (net (code "183") (name "unconnected-(X8L-S-Pad2)") (class "Default")
      (node (ref "X8") (pin "2") (pinfunction "S_2") (pintype "passive"))
    )
    (net (code "184") (name "unconnected-(X8M-S-Pad20)") (class "Default")
      (node (ref "X8") (pin "20") (pinfunction "S_20") (pintype "passive"))
    )
    (net (code "185") (name "unconnected-(X8O-S-Pad22)") (class "Default")
      (node (ref "X8") (pin "22") (pinfunction "S_22") (pintype "passive"))
    )
    (net (code "186") (name "unconnected-(X8P-S-Pad23)") (class "Default")
      (node (ref "X8") (pin "23") (pinfunction "S_23") (pintype "passive"))
    )
    (net (code "187") (name "unconnected-(X8Q-S-Pad24)") (class "Default")
      (node (ref "X8") (pin "24") (pinfunction "S_24") (pintype "passive"))
    )
    (net (code "188") (name "unconnected-(X8R-S-Pad3)") (class "Default")
      (node (ref "X8") (pin "3") (pinfunction "S_3") (pintype "passive"))
    )
    (net (code "189") (name "unconnected-(X8S-S-Pad4)") (class "Default")
      (node (ref "X8") (pin "4") (pinfunction "S_4") (pintype "passive"))
    )
    (net (code "190") (name "unconnected-(X8T-S-Pad5)") (class "Default")
      (node (ref "X8") (pin "5") (pinfunction "S_5") (pintype "passive"))
    )
    (net (code "191") (name "unconnected-(X8U-S-Pad6)") (class "Default")
      (node (ref "X8") (pin "6") (pinfunction "S_6") (pintype "passive"))
    )
    (net (code "192") (name "unconnected-(X8V-S-Pad7)") (class "Default")
      (node (ref "X8") (pin "7") (pinfunction "S_7") (pintype "passive"))
    )
    (net (code "193") (name "unconnected-(X8W-S-Pad8)") (class "Default")
      (node (ref "X8") (pin "8") (pinfunction "S_8") (pintype "passive"))
    )
  )
)
